# CMSIS-DAP-Pro.net
KiCad netlist of a schematic drawn in Altium Designer
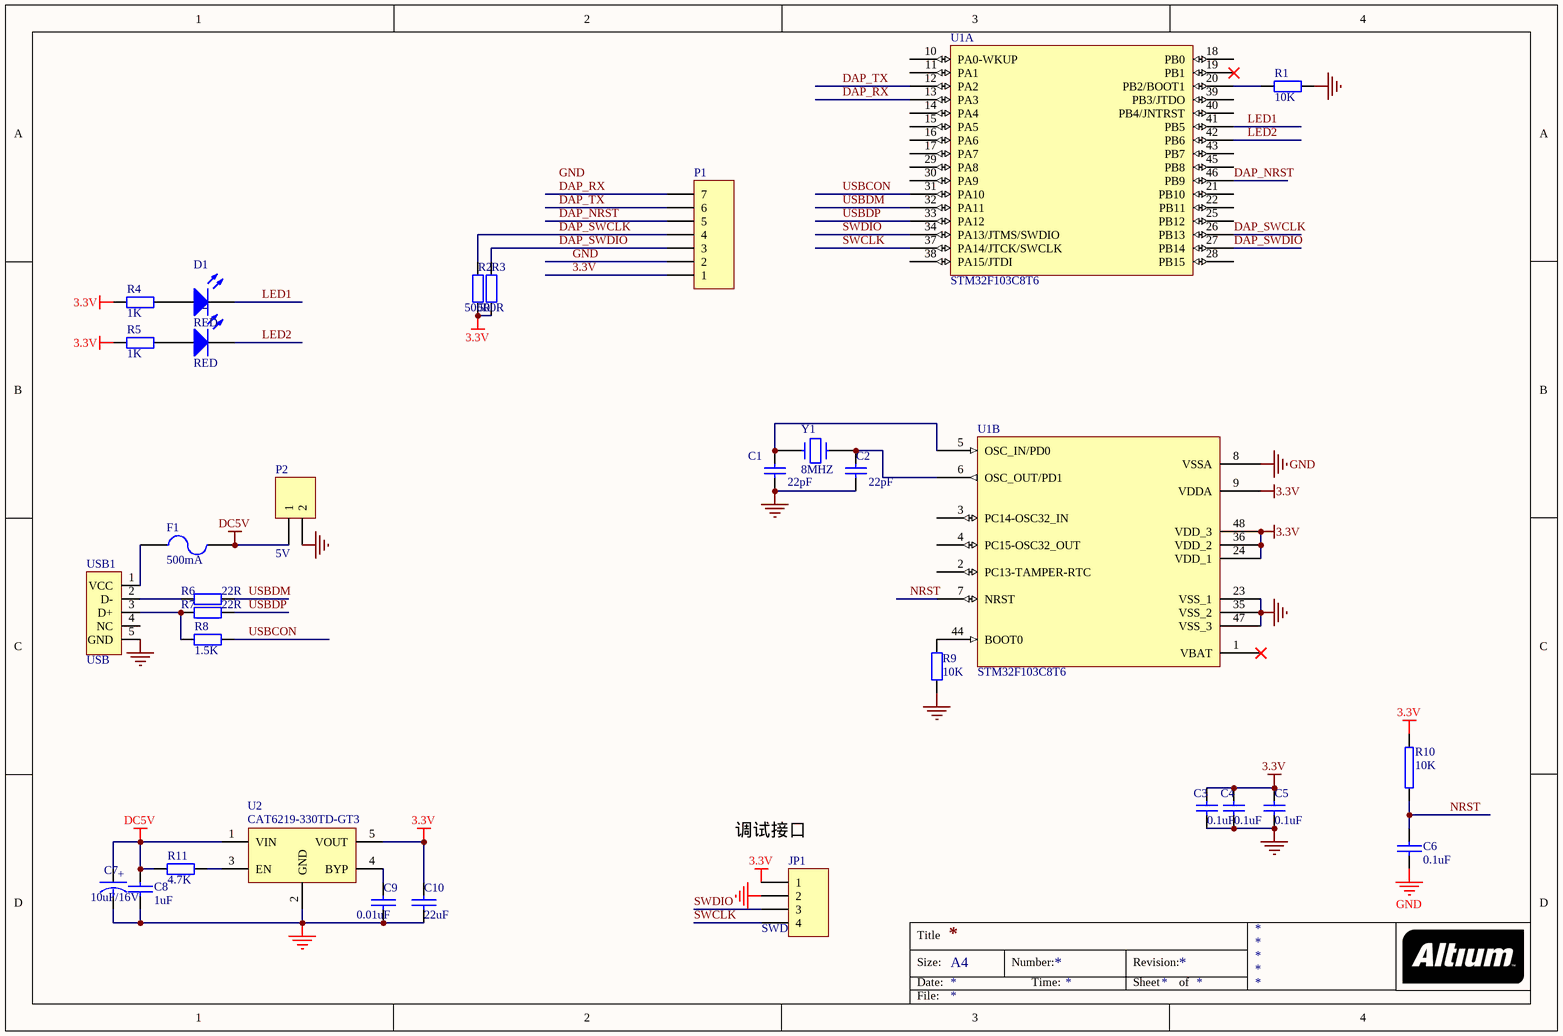
[diagram p0: CMSIS-DAP-Pro.SchDoc]

(export (version "E")
  (design (tool "Eeschema 10.0.6"))
  (components
    (comp (ref "C1")
      (value "22pF")
      (footprint "0603C")
      (description "Capacitor")
      (fields (field (name "PUBLISHER") "Altium Limited"))
      (libsource (lib "智嵌 STM32F407Z开发板（企业型）") (part "Cap"))
    )
    (comp (ref "C2")
      (value "22pF")
      (footprint "0603C")
      (description "Capacitor")
      (fields (field (name "PUBLISHER") "Altium Limited"))
      (libsource (lib "智嵌 STM32F407Z开发板（企业型）") (part "Cap"))
    )
    (comp (ref "C3")
      (value "0.1uF")
      (footprint "0603C")
      (description "Capacitor")
      (fields (field (name "PUBLISHER") "Altium Limited"))
      (libsource (lib "Miscellaneous Devices") (part "Cap"))
    )
    (comp (ref "C4")
      (value "0.1uF")
      (footprint "0603C")
      (description "Capacitor")
      (fields (field (name "PUBLISHER") "Altium Limited"))
      (libsource (lib "Miscellaneous Devices") (part "Cap"))
    )
    (comp (ref "C5")
      (value "0.1uF")
      (footprint "0603C")
      (description "Capacitor")
      (fields (field (name "PUBLISHER") "Altium Limited"))
      (libsource (lib "Miscellaneous Devices") (part "Cap"))
    )
    (comp (ref "C6")
      (value "0.1uF")
      (footprint "0603C")
      (description "Capacitor")
      (libsource (lib "LPC11xx(L)FDH20封装库") (part "CAP"))
    )
    (comp (ref "C7")
      (value "10uF/16V")
      (footprint "CAP-A")
      (description "Capacitor")
      (libsource (lib "LPC11xx_System_Sch_AD") (part "CAPACITOR POL"))
    )
    (comp (ref "C8")
      (value "1uF")
      (footprint "0603C")
      (description "Capacitor")
      (libsource (lib "LPC11xx_System_Sch_AD") (part "CAP"))
    )
    (comp (ref "C9")
      (value "0.01uF")
      (footprint "0603C")
      (description "Capacitor")
      (libsource (lib "LPC11xx_System_Sch_AD") (part "CAP"))
    )
    (comp (ref "C10")
      (value "22uF")
      (footprint "0603C")
      (description "Capacitor")
      (libsource (lib "LPC11xx_System_Sch_AD") (part "CAP"))
    )
    (comp (ref "D1")
      (value "RED")
      (footprint "LED-0805")
      (description "Typical INFRARED GaAs LED")
      (fields (field (name "PUBLISHER") "Altium Limited"))
      (libsource (lib "Miscellaneous Devices") (part "LED0"))
    )
    (comp (ref "D2")
      (value "RED")
      (footprint "LED-0805")
      (description "Typical INFRARED GaAs LED")
      (fields (field (name "PUBLISHER") "Altium Limited"))
      (libsource (lib "Miscellaneous Devices") (part "LED0"))
    )
    (comp (ref "F1")
      (value "500mA")
      (footprint "0805")
      (description "Fuse")
      (fields (field (name "PUBLISHER") "Altium Limited"))
      (libsource (lib "Miscellaneous Devices") (part "Fuse 2"))
    )
    (comp (ref "JP1")
      (value "SWD")
      (footprint "PH2-4P")
      (description "Header, 4-Pin")
      (fields (field (name "PUBLISHER") "Altium Limited"))
      (libsource (lib "Miscellaneous Connectors") (part "Header 4"))
    )
    (comp (ref "P1")
      (value "Header 7")
      (footprint "PH-7P-1.25mm")
      (description "Header, 7-Pin")
      (fields (field (name "PUBLISHER") "Altium Limited"))
      (libsource (lib "Miscellaneous Connectors") (part "Header 7"))
    )
    (comp (ref "P2")
      (value "5V")
      (footprint "HDR1X2")
      (description "Header, 2-Pin")
      (fields (field (name "PUBLISHER") "Altium Limited"))
      (libsource (lib "Miscellaneous Connectors") (part "Header 2"))
    )
    (comp (ref "R1")
      (value "10K")
      (footprint "0603R")
      (description "Resistor")
      (fields (field (name "PUBLISHER") "Altium Limited"))
      (libsource (lib "") (part "Res2_1"))
    )
    (comp (ref "R2")
      (value "500R")
      (footprint "0603R")
      (description "Resistor")
      (fields (field (name "PUBLISHER") "Altium Limited"))
      (libsource (lib "") (part "Res2_2"))
    )
    (comp (ref "R3")
      (value "500R")
      (footprint "0603R")
      (description "Resistor")
      (fields (field (name "PUBLISHER") "Altium Limited"))
      (libsource (lib "") (part "Res2_2"))
    )
    (comp (ref "R4")
      (value "1K")
      (footprint "0603R")
      (description "Resistor")
      (fields (field (name "PUBLISHER") "Altium Limited"))
      (libsource (lib "Miscellaneous Devices") (part "Res2"))
    )
    (comp (ref "R5")
      (value "1K")
      (footprint "0603R")
      (description "Resistor")
      (fields (field (name "PUBLISHER") "Altium Limited"))
      (libsource (lib "Miscellaneous Devices") (part "Res2"))
    )
    (comp (ref "R6")
      (value "22R")
      (footprint "0603R")
      (description "Resistor")
      (fields (field (name "PUBLISHER") "Altium Limited"))
      (libsource (lib "Miscellaneous Devices") (part "Res2"))
    )
    (comp (ref "R7")
      (value "22R")
      (footprint "0603R")
      (description "Resistor")
      (fields (field (name "PUBLISHER") "Altium Limited"))
      (libsource (lib "Miscellaneous Devices") (part "Res2"))
    )
    (comp (ref "R8")
      (value "1.5K")
      (footprint "0603R")
      (description "贴片电阻")
      (fields (field (name "Comment") "Res1") (field (name "PUBLISHER") "Altium Limited"))
      (libsource (lib "Fszhang") (part "Res1"))
    )
    (comp (ref "R9")
      (value "10K")
      (footprint "0603R")
      (description "Resistor")
      (fields (field (name "PUBLISHER") "Altium Limited"))
      (libsource (lib "Miscellaneous Devices") (part "Res2"))
    )
    (comp (ref "R10") (value "10K") (footprint "0603R") (libsource (lib "LPC11xx(L)FDH20封装库") (part "RES2")))
    (comp (ref "R11")
      (value "4.7K")
      (footprint "0603R")
      (description "Resistor")
      (fields (field (name "PUBLISHER") "Altium Limited"))
      (libsource (lib "") (part "Res2_1"))
    )
    (comp (ref "U1")
      (value "STM32F103C8T6")
      (footprint "LQFP48_L")
      (description "STM32 ARM-based 32-bit MCU with 64 Kbytes Flash, 48-pin LQFP, Industrial Temperature")
      (libsource (lib "RFID") (part "STM32F103C8T6"))
    )
    (comp (ref "U2")
      (value "CAT6219-330TD-GT3")
      (footprint "SOT-23-5")
      (description "Connector")
      (libsource (lib "LPC11xx_System_Sch_AD") (part "CAT6219"))
    )
    (comp (ref "USB1")
      (value "USB")
      (footprint "USB_MINIB_SMT")
      (libsource (lib "MiniSTM32+V3.0%E5%B0%81%E8%A3%85%E5%BA%93") (part "USB5"))
    )
    (comp (ref "Y1")
      (value "8MHZ")
      (footprint "SMD-5032_2P")
      (description "Crystal")
      (libsource (lib "智嵌 STM32F407Z开发板（企业型）") (part "CRYSTAL"))
    )
  )
  (nets
    (net (code "1") (name "/DAP_NRST") (class "Default")
      (node (ref "P1") (pin "5") (pinfunction "5_5") (pintype "passive"))
      (node (ref "U1") (pin "46") (pinfunction "PB9_46") (pintype "bidirectional"))
    )
    (net (code "2") (name "/DAP_RX") (class "Default")
      (node (ref "P1") (pin "7") (pinfunction "7_7") (pintype "passive"))
      (node (ref "U1") (pin "13") (pinfunction "PA3_13") (pintype "bidirectional"))
    )
    (net (code "3") (name "/DAP_SWCLK") (class "Default")
      (node (ref "P1") (pin "4") (pinfunction "4_4") (pintype "passive"))
      (node (ref "R2") (pin "1") (pinfunction "1_1") (pintype "passive"))
      (node (ref "U1") (pin "26") (pinfunction "PB13_26") (pintype "bidirectional"))
    )
    (net (code "4") (name "/DAP_SWDIO") (class "Default")
      (node (ref "P1") (pin "3") (pinfunction "3_3") (pintype "passive"))
      (node (ref "R3") (pin "1") (pinfunction "1_1") (pintype "passive"))
      (node (ref "U1") (pin "27") (pinfunction "PB14_27") (pintype "bidirectional"))
    )
    (net (code "5") (name "/DAP_TX") (class "Default")
      (node (ref "P1") (pin "6") (pinfunction "6_6") (pintype "passive"))
      (node (ref "U1") (pin "12") (pinfunction "PA2_12") (pintype "bidirectional"))
    )
    (net (code "6") (name "/LED1") (class "Default")
      (node (ref "D1") (pin "2") (pinfunction "K_2") (pintype "passive"))
      (node (ref "U1") (pin "41") (pinfunction "PB5_41") (pintype "bidirectional"))
    )
    (net (code "7") (name "/LED2") (class "Default")
      (node (ref "D2") (pin "2") (pinfunction "K_2") (pintype "passive"))
      (node (ref "U1") (pin "42") (pinfunction "PB6_42") (pintype "bidirectional"))
    )
    (net (code "8") (name "/NRST") (class "Default")
      (node (ref "C6") (pin "2") (pinfunction "2_2") (pintype "passive"))
      (node (ref "R10") (pin "1") (pinfunction "1_1") (pintype "passive"))
      (node (ref "U1") (pin "7") (pinfunction "NRST_7") (pintype "bidirectional"))
    )
    (net (code "9") (name "/SWCLK") (class "Default")
      (node (ref "JP1") (pin "4") (pinfunction "4_4") (pintype "passive"))
      (node (ref "U1") (pin "37") (pinfunction "PA14/JTCK/SWCLK_37") (pintype "bidirectional"))
    )
    (net (code "10") (name "/SWDIO") (class "Default")
      (node (ref "JP1") (pin "3") (pinfunction "3_3") (pintype "passive"))
      (node (ref "U1") (pin "34") (pinfunction "PA13/JTMS/SWDIO_34") (pintype "bidirectional"))
    )
    (net (code "11") (name "/USBCON") (class "Default")
      (node (ref "R8") (pin "2") (pinfunction "2_2") (pintype "passive"))
      (node (ref "U1") (pin "31") (pinfunction "PA10_31") (pintype "bidirectional"))
    )
    (net (code "12") (name "/USBDM") (class "Default")
      (node (ref "R6") (pin "1") (pinfunction "1_1") (pintype "passive"))
      (node (ref "U1") (pin "32") (pinfunction "PA11_32") (pintype "bidirectional"))
    )
    (net (code "13") (name "/USBDP") (class "Default")
      (node (ref "R7") (pin "1") (pinfunction "1_1") (pintype "passive"))
      (node (ref "U1") (pin "33") (pinfunction "PA12_33") (pintype "bidirectional"))
    )
    (net (code "14") (name "3.3V") (class "Default")
      (node (ref "C10") (pin "1") (pinfunction "1_1") (pintype "passive"))
      (node (ref "C3") (pin "2") (pinfunction "2_2") (pintype "passive"))
      (node (ref "C4") (pin "2") (pinfunction "2_2") (pintype "passive"))
      (node (ref "C5") (pin "2") (pinfunction "2_2") (pintype "passive"))
      (node (ref "JP1") (pin "1") (pinfunction "1_1") (pintype "passive"))
      (node (ref "P1") (pin "1") (pinfunction "1_1") (pintype "passive"))
      (node (ref "R10") (pin "2") (pinfunction "2_2") (pintype "passive"))
      (node (ref "R2") (pin "2") (pinfunction "2_2") (pintype "passive"))
      (node (ref "R3") (pin "2") (pinfunction "2_2") (pintype "passive"))
      (node (ref "R4") (pin "2") (pinfunction "2_2") (pintype "passive"))
      (node (ref "R5") (pin "2") (pinfunction "2_2") (pintype "passive"))
      (node (ref "U1") (pin "24") (pinfunction "VDD_1_24") (pintype "power_in"))
      (node (ref "U1") (pin "36") (pinfunction "VDD_2_36") (pintype "power_in"))
      (node (ref "U1") (pin "48") (pinfunction "VDD_3_48") (pintype "power_in"))
      (node (ref "U1") (pin "9") (pinfunction "VDDA_9") (pintype "power_in"))
      (node (ref "U2") (pin "5") (pinfunction "VOUT_5") (pintype "passive"))
    )
    (net (code "15") (name "DC5V") (class "Default")
      (node (ref "C7") (pin "1") (pinfunction "1_1") (pintype "passive"))
      (node (ref "C8") (pin "1") (pinfunction "1_1") (pintype "passive"))
      (node (ref "F1") (pin "2") (pinfunction "2_2") (pintype "passive"))
      (node (ref "P2") (pin "1") (pinfunction "1_1") (pintype "passive"))
      (node (ref "R11") (pin "1") (pinfunction "1_1") (pintype "passive"))
      (node (ref "U2") (pin "1") (pinfunction "VIN_1") (pintype "passive"))
    )
    (net (code "16") (name "GND") (class "Default")
      (node (ref "C1") (pin "1") (pinfunction "1_1") (pintype "passive"))
      (node (ref "C10") (pin "2") (pinfunction "2_2") (pintype "passive"))
      (node (ref "C2") (pin "1") (pinfunction "1_1") (pintype "passive"))
      (node (ref "C3") (pin "1") (pinfunction "1_1") (pintype "passive"))
      (node (ref "C4") (pin "1") (pinfunction "1_1") (pintype "passive"))
      (node (ref "C5") (pin "1") (pinfunction "1_1") (pintype "passive"))
      (node (ref "C6") (pin "1") (pinfunction "1_1") (pintype "passive"))
      (node (ref "C7") (pin "2") (pinfunction "2_2") (pintype "passive"))
      (node (ref "C8") (pin "2") (pinfunction "2_2") (pintype "passive"))
      (node (ref "C9") (pin "2") (pinfunction "2_2") (pintype "passive"))
      (node (ref "JP1") (pin "2") (pinfunction "2_2") (pintype "passive"))
      (node (ref "P1") (pin "2") (pinfunction "2_2") (pintype "passive"))
      (node (ref "P2") (pin "2") (pinfunction "2_2") (pintype "passive"))
      (node (ref "R1") (pin "2") (pinfunction "2_2") (pintype "passive"))
      (node (ref "R9") (pin "2") (pinfunction "2_2") (pintype "passive"))
      (node (ref "U1") (pin "23") (pinfunction "VSS_1_23") (pintype "power_in"))
      (node (ref "U1") (pin "35") (pinfunction "VSS_2_35") (pintype "power_in"))
      (node (ref "U1") (pin "47") (pinfunction "VSS_3_47") (pintype "power_in"))
      (node (ref "U1") (pin "8") (pinfunction "VSSA_8") (pintype "power_in"))
      (node (ref "U2") (pin "2") (pinfunction "GND_2") (pintype "passive"))
      (node (ref "USB1") (pin "5") (pinfunction "GND_5") (pintype "passive"))
    )
    (net (code "17") (name "Net-(D1-A)") (class "Default")
      (node (ref "D1") (pin "1") (pinfunction "A_1") (pintype "passive"))
      (node (ref "R4") (pin "1") (pinfunction "1_1") (pintype "passive"))
    )
    (net (code "18") (name "Net-(D2-A)") (class "Default")
      (node (ref "D2") (pin "1") (pinfunction "A_1") (pintype "passive"))
      (node (ref "R5") (pin "1") (pinfunction "1_1") (pintype "passive"))
    )
    (net (code "19") (name "Net-(U1A-PB2{slash}BOOT1)") (class "Default")
      (node (ref "R1") (pin "1") (pinfunction "1_1") (pintype "passive"))
      (node (ref "U1") (pin "20") (pinfunction "PB2/BOOT1_20") (pintype "bidirectional"))
    )
    (net (code "20") (name "Net-(U1B-BOOT0)") (class "Default")
      (node (ref "R9") (pin "1") (pinfunction "1_1") (pintype "passive"))
      (node (ref "U1") (pin "44") (pinfunction "BOOT0_44") (pintype "input"))
    )
    (net (code "21") (name "Net-(U1B-OSC_IN{slash}PD0)") (class "Default")
      (node (ref "C1") (pin "2") (pinfunction "2_2") (pintype "passive"))
      (node (ref "U1") (pin "5") (pinfunction "OSC_IN/PD0_5") (pintype "input"))
      (node (ref "Y1") (pin "1") (pinfunction "1_1") (pintype "passive"))
    )
    (net (code "22") (name "Net-(U1B-OSC_OUT{slash}PD1)") (class "Default")
      (node (ref "C2") (pin "2") (pinfunction "2_2") (pintype "passive"))
      (node (ref "U1") (pin "6") (pinfunction "OSC_OUT/PD1_6") (pintype "output"))
      (node (ref "Y1") (pin "2") (pinfunction "2_2") (pintype "passive"))
    )
    (net (code "23") (name "Net-(U2-BYP)") (class "Default")
      (node (ref "C9") (pin "1") (pinfunction "1_1") (pintype "passive"))
      (node (ref "U2") (pin "4") (pinfunction "BYP_4") (pintype "passive"))
    )
    (net (code "24") (name "Net-(U2-EN)") (class "Default")
      (node (ref "R11") (pin "2") (pinfunction "2_2") (pintype "passive"))
      (node (ref "U2") (pin "3") (pinfunction "EN_3") (pintype "passive"))
    )
    (net (code "25") (name "Net-(USB1-D+)") (class "Default")
      (node (ref "R7") (pin "2") (pinfunction "2_2") (pintype "passive"))
      (node (ref "R8") (pin "1") (pinfunction "1_1") (pintype "passive"))
      (node (ref "USB1") (pin "3") (pinfunction "D+_3") (pintype "passive"))
    )
    (net (code "26") (name "Net-(USB1-D-)") (class "Default")
      (node (ref "R6") (pin "2") (pinfunction "2_2") (pintype "passive"))
      (node (ref "USB1") (pin "2") (pinfunction "D-_2") (pintype "passive"))
    )
    (net (code "27") (name "Net-(USB1-VCC)") (class "Default")
      (node (ref "F1") (pin "1") (pinfunction "1_1") (pintype "passive"))
      (node (ref "USB1") (pin "1") (pinfunction "VCC_1") (pintype "passive"))
    )
    (net (code "28") (name "unconnected-(U1A-PA0-WKUP-Pad10)") (class "Default")
      (node (ref "U1") (pin "10") (pinfunction "PA0-WKUP_10") (pintype "bidirectional"))
    )
    (net (code "29") (name "unconnected-(U1A-PA1-Pad11)") (class "Default")
      (node (ref "U1") (pin "11") (pinfunction "PA1_11") (pintype "bidirectional"))
    )
    (net (code "30") (name "unconnected-(U1A-PA4-Pad14)") (class "Default")
      (node (ref "U1") (pin "14") (pinfunction "PA4_14") (pintype "bidirectional"))
    )
    (net (code "31") (name "unconnected-(U1A-PA5-Pad15)") (class "Default")
      (node (ref "U1") (pin "15") (pinfunction "PA5_15") (pintype "bidirectional"))
    )
    (net (code "32") (name "unconnected-(U1A-PA6-Pad16)") (class "Default")
      (node (ref "U1") (pin "16") (pinfunction "PA6_16") (pintype "bidirectional"))
    )
    (net (code "33") (name "unconnected-(U1A-PA7-Pad17)") (class "Default")
      (node (ref "U1") (pin "17") (pinfunction "PA7_17") (pintype "bidirectional"))
    )
    (net (code "34") (name "unconnected-(U1A-PA8-Pad29)") (class "Default")
      (node (ref "U1") (pin "29") (pinfunction "PA8_29") (pintype "bidirectional"))
    )
    (net (code "35") (name "unconnected-(U1A-PA9-Pad30)") (class "Default")
      (node (ref "U1") (pin "30") (pinfunction "PA9_30") (pintype "bidirectional"))
    )
    (net (code "36") (name "unconnected-(U1A-PA15{slash}JTDI-Pad38)") (class "Default")
      (node (ref "U1") (pin "38") (pinfunction "PA15/JTDI_38") (pintype "bidirectional"))
    )
    (net (code "37") (name "unconnected-(U1A-PB0-Pad18)") (class "Default")
      (node (ref "U1") (pin "18") (pinfunction "PB0_18") (pintype "bidirectional"))
    )
    (net (code "38") (name "unconnected-(U1A-PB1-Pad19)") (class "Default")
      (node (ref "U1") (pin "19") (pinfunction "PB1_19") (pintype "bidirectional+no_connect"))
    )
    (net (code "39") (name "unconnected-(U1A-PB3{slash}JTDO-Pad39)") (class "Default")
      (node (ref "U1") (pin "39") (pinfunction "PB3/JTDO_39") (pintype "bidirectional"))
    )
    (net (code "40") (name "unconnected-(U1A-PB4{slash}JNTRST-Pad40)") (class "Default")
      (node (ref "U1") (pin "40") (pinfunction "PB4/JNTRST_40") (pintype "bidirectional"))
    )
    (net (code "41") (name "unconnected-(U1A-PB7-Pad43)") (class "Default")
      (node (ref "U1") (pin "43") (pinfunction "PB7_43") (pintype "bidirectional"))
    )
    (net (code "42") (name "unconnected-(U1A-PB8-Pad45)") (class "Default")
      (node (ref "U1") (pin "45") (pinfunction "PB8_45") (pintype "bidirectional"))
    )
    (net (code "43") (name "unconnected-(U1A-PB10-Pad21)") (class "Default")
      (node (ref "U1") (pin "21") (pinfunction "PB10_21") (pintype "bidirectional"))
    )
    (net (code "44") (name "unconnected-(U1A-PB11-Pad22)") (class "Default")
      (node (ref "U1") (pin "22") (pinfunction "PB11_22") (pintype "bidirectional"))
    )
    (net (code "45") (name "unconnected-(U1A-PB12-Pad25)") (class "Default")
      (node (ref "U1") (pin "25") (pinfunction "PB12_25") (pintype "bidirectional"))
    )
    (net (code "46") (name "unconnected-(U1A-PB15-Pad28)") (class "Default")
      (node (ref "U1") (pin "28") (pinfunction "PB15_28") (pintype "bidirectional"))
    )
    (net (code "47") (name "unconnected-(U1B-PC13-TAMPER-RTC-Pad2)") (class "Default")
      (node (ref "U1") (pin "2") (pinfunction "PC13-TAMPER-RTC_2") (pintype "bidirectional"))
    )
    (net (code "48") (name "unconnected-(U1B-PC14-OSC32_IN-Pad3)") (class "Default")
      (node (ref "U1") (pin "3") (pinfunction "PC14-OSC32_IN_3") (pintype "bidirectional"))
    )
    (net (code "49") (name "unconnected-(U1B-PC15-OSC32_OUT-Pad4)") (class "Default")
      (node (ref "U1") (pin "4") (pinfunction "PC15-OSC32_OUT_4") (pintype "bidirectional"))
    )
    (net (code "50") (name "unconnected-(U1B-VBAT-Pad1)") (class "Default")
      (node (ref "U1") (pin "1") (pinfunction "VBAT_1") (pintype "power_in+no_connect"))
    )
    (net (code "51") (name "unconnected-(USB1-NC-Pad4)") (class "Default")
      (node (ref "USB1") (pin "4") (pinfunction "NC_4") (pintype "passive"))
    )
  )
)
